# SigueLinea-final-SIN-PLANO-GND.net
KiCad netlist of a schematic drawn in EAGLE
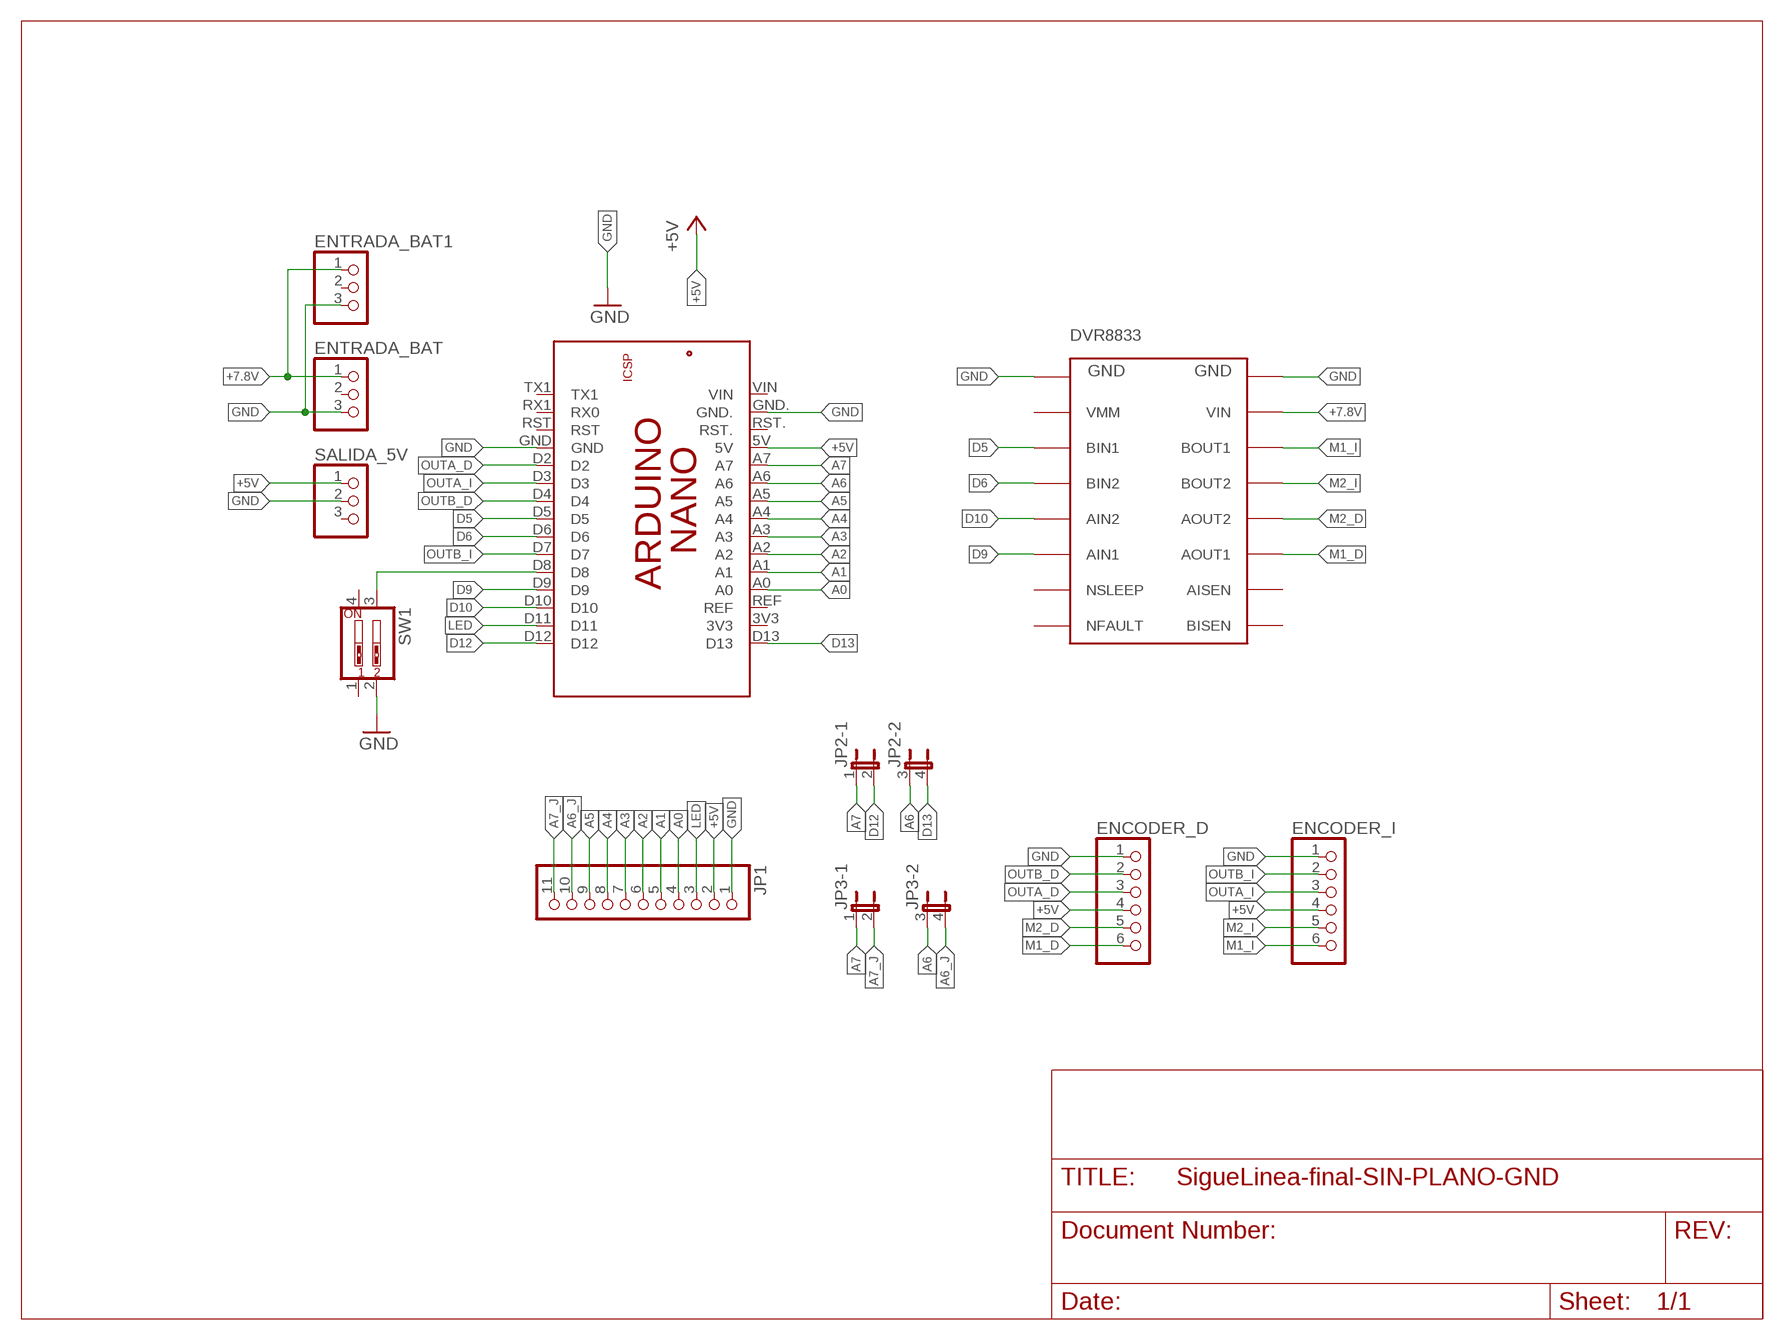
[diagram p0: schematic, sheet 1]

(export (version "E")
  (design (tool "Eeschema 10.0.6"))
  (components
    (comp (ref "DVR8833")
      (value "DRV8833")
      (footprint "eagle-import:DRV8833")
      (libsource (lib "eagle-import") (part "DRV8833"))
    )
    (comp (ref "ENCODER_D")
      (value "PINHD-1X6")
      (footprint "eagle-import:1X06")
      (libsource (lib "eagle-import") (part "PINHD-1X6"))
    )
    (comp (ref "ENCODER_I")
      (value "PINHD-1X6")
      (footprint "eagle-import:1X06")
      (libsource (lib "eagle-import") (part "PINHD-1X6"))
    )
    (comp (ref "ENTRADA_BAT")
      (value "PINHD-1X3")
      (footprint "eagle-import:1X03")
      (libsource (lib "eagle-import") (part "PINHD-1X3"))
    )
    (comp (ref "ENTRADA_BAT1")
      (value "PINHD-1X3")
      (footprint "eagle-import:1X03")
      (libsource (lib "eagle-import") (part "PINHD-1X3"))
    )
    (comp (ref "JP1")
      (value "PINHD-1X11")
      (footprint "eagle-import:1X11")
      (libsource (lib "eagle-import") (part "PINHD-1X11"))
    )
    (comp (ref "JP2")
      (value "JP2QE")
      (footprint "eagle-import:JP2Q")
      (libsource (lib "eagle-import") (part "JP2QE"))
    )
    (comp (ref "JP3")
      (value "JP2QE")
      (footprint "eagle-import:JP2Q")
      (libsource (lib "eagle-import") (part "JP2QE"))
    )
    (comp (ref "PCB1")
      (value "ARDUINO_NANO")
      (footprint "eagle-import:ARDUINO_NANO")
      (libsource (lib "eagle-import") (part "ARDUINO_NANO"))
    )
    (comp (ref "SALIDA_5V")
      (value "PINHD-1X3")
      (footprint "eagle-import:1X03")
      (libsource (lib "eagle-import") (part "PINHD-1X3"))
    )
    (comp (ref "SW1")
      (value "SW_DIP-2")
      (footprint "eagle-import:EDG-02")
      (libsource (lib "eagle-import") (part "SW_DIP-2"))
    )
  )
  (nets
    (net (code "1") (name "+5V") (class "Default")
      (node (ref "ENCODER_D") (pin "4") (pinfunction "4_4") (pintype "passive"))
      (node (ref "ENCODER_I") (pin "4") (pinfunction "4_4") (pintype "passive"))
      (node (ref "JP1") (pin "2") (pinfunction "2_2") (pintype "passive"))
      (node (ref "PCB1") (pin "5V") (pinfunction "5V_5V") (pintype "bidirectional"))
      (node (ref "SALIDA_5V") (pin "1") (pinfunction "1_1") (pintype "passive"))
    )
    (net (code "2") (name "+7.8V") (class "Default")
      (node (ref "DVR8833") (pin "VIN") (pinfunction "VIN_VIN") (pintype "bidirectional"))
      (node (ref "ENTRADA_BAT") (pin "1") (pinfunction "1_1") (pintype "passive"))
      (node (ref "ENTRADA_BAT1") (pin "1") (pinfunction "1_1") (pintype "passive"))
    )
    (net (code "3") (name "A0") (class "Default")
      (node (ref "JP1") (pin "4") (pinfunction "4_4") (pintype "passive"))
      (node (ref "PCB1") (pin "A0") (pinfunction "A0_A0") (pintype "bidirectional"))
    )
    (net (code "4") (name "A1") (class "Default")
      (node (ref "JP1") (pin "5") (pinfunction "5_5") (pintype "passive"))
      (node (ref "PCB1") (pin "A1") (pinfunction "A1_A1") (pintype "bidirectional"))
    )
    (net (code "5") (name "A2") (class "Default")
      (node (ref "JP1") (pin "6") (pinfunction "6_6") (pintype "passive"))
      (node (ref "PCB1") (pin "A2") (pinfunction "A2_A2") (pintype "bidirectional"))
    )
    (net (code "6") (name "A3") (class "Default")
      (node (ref "JP1") (pin "7") (pinfunction "7_7") (pintype "passive"))
      (node (ref "PCB1") (pin "A3") (pinfunction "A3_A3") (pintype "bidirectional"))
    )
    (net (code "7") (name "A4") (class "Default")
      (node (ref "JP1") (pin "8") (pinfunction "8_8") (pintype "passive"))
      (node (ref "PCB1") (pin "A4") (pinfunction "A4_A4") (pintype "bidirectional"))
    )
    (net (code "8") (name "A5") (class "Default")
      (node (ref "JP1") (pin "9") (pinfunction "9_9") (pintype "passive"))
      (node (ref "PCB1") (pin "A5") (pinfunction "A5_A5") (pintype "bidirectional"))
    )
    (net (code "9") (name "A6") (class "Default")
      (node (ref "JP2") (pin "3") (pinfunction "1_3") (pintype "passive"))
      (node (ref "JP3") (pin "3") (pinfunction "1_3") (pintype "passive"))
      (node (ref "PCB1") (pin "A6") (pinfunction "A6_A6") (pintype "bidirectional"))
    )
    (net (code "10") (name "A6_J") (class "Default")
      (node (ref "JP1") (pin "10") (pinfunction "10_10") (pintype "passive"))
      (node (ref "JP3") (pin "4") (pinfunction "2_4") (pintype "passive"))
    )
    (net (code "11") (name "A7") (class "Default")
      (node (ref "JP2") (pin "1") (pinfunction "1_1") (pintype "passive"))
      (node (ref "JP3") (pin "1") (pinfunction "1_1") (pintype "passive"))
      (node (ref "PCB1") (pin "A7") (pinfunction "A7_A7") (pintype "bidirectional"))
    )
    (net (code "12") (name "A7_J") (class "Default")
      (node (ref "JP1") (pin "11") (pinfunction "11_11") (pintype "passive"))
      (node (ref "JP3") (pin "2") (pinfunction "2_2") (pintype "passive"))
    )
    (net (code "13") (name "D5") (class "Default")
      (node (ref "DVR8833") (pin "BIN1") (pinfunction "BIN1_BIN1") (pintype "bidirectional"))
      (node (ref "PCB1") (pin "D5") (pinfunction "D5_D5") (pintype "bidirectional"))
    )
    (net (code "14") (name "D6") (class "Default")
      (node (ref "DVR8833") (pin "BIN2") (pinfunction "BIN2_BIN2") (pintype "bidirectional"))
      (node (ref "PCB1") (pin "D6") (pinfunction "D6_D6") (pintype "bidirectional"))
    )
    (net (code "15") (name "D9") (class "Default")
      (node (ref "DVR8833") (pin "AIN1") (pinfunction "AIN1_AIN1") (pintype "bidirectional"))
      (node (ref "PCB1") (pin "D9") (pinfunction "D9_D9") (pintype "bidirectional"))
    )
    (net (code "16") (name "D10") (class "Default")
      (node (ref "DVR8833") (pin "AIN2") (pinfunction "AIN2_AIN2") (pintype "bidirectional"))
      (node (ref "PCB1") (pin "D10") (pinfunction "D10_D10") (pintype "bidirectional"))
    )
    (net (code "17") (name "D12") (class "Default")
      (node (ref "JP2") (pin "2") (pinfunction "2_2") (pintype "passive"))
      (node (ref "PCB1") (pin "D12") (pinfunction "D12_D12") (pintype "bidirectional"))
    )
    (net (code "18") (name "D13") (class "Default")
      (node (ref "JP2") (pin "4") (pinfunction "2_4") (pintype "passive"))
      (node (ref "PCB1") (pin "D13") (pinfunction "D13_D13") (pintype "bidirectional"))
    )
    (net (code "19") (name "GND") (class "Default")
      (node (ref "DVR8833") (pin "GND1") (pinfunction "GND1_GND1") (pintype "bidirectional"))
      (node (ref "DVR8833") (pin "GND2") (pinfunction "GND2_GND2") (pintype "bidirectional"))
      (node (ref "ENCODER_D") (pin "1") (pinfunction "1_1") (pintype "passive"))
      (node (ref "ENCODER_I") (pin "1") (pinfunction "1_1") (pintype "passive"))
      (node (ref "ENTRADA_BAT") (pin "3") (pinfunction "3_3") (pintype "passive"))
      (node (ref "ENTRADA_BAT1") (pin "3") (pinfunction "3_3") (pintype "passive"))
      (node (ref "JP1") (pin "1") (pinfunction "1_1") (pintype "passive"))
      (node (ref "PCB1") (pin "GND") (pinfunction "GND_GND") (pintype "bidirectional"))
      (node (ref "PCB1") (pin "GND.") (pinfunction "GND._GND.") (pintype "bidirectional"))
      (node (ref "SALIDA_5V") (pin "2") (pinfunction "2_2") (pintype "passive"))
      (node (ref "SW1") (pin "2") (pinfunction "2_2") (pintype "passive"))
    )
    (net (code "20") (name "LED") (class "Default")
      (node (ref "JP1") (pin "3") (pinfunction "3_3") (pintype "passive"))
      (node (ref "PCB1") (pin "D11") (pinfunction "D11_D11") (pintype "bidirectional"))
    )
    (net (code "21") (name "M1_D") (class "Default")
      (node (ref "DVR8833") (pin "AOUT1") (pinfunction "AOUT1_AOUT1") (pintype "bidirectional"))
      (node (ref "ENCODER_D") (pin "6") (pinfunction "6_6") (pintype "passive"))
    )
    (net (code "22") (name "M1_I") (class "Default")
      (node (ref "DVR8833") (pin "BOUT1") (pinfunction "BOUT1_BOUT1") (pintype "bidirectional"))
      (node (ref "ENCODER_I") (pin "6") (pinfunction "6_6") (pintype "passive"))
    )
    (net (code "23") (name "M2_D") (class "Default")
      (node (ref "DVR8833") (pin "AOUT2") (pinfunction "AOUT2_AOUT2") (pintype "bidirectional"))
      (node (ref "ENCODER_D") (pin "5") (pinfunction "5_5") (pintype "passive"))
    )
    (net (code "24") (name "M2_I") (class "Default")
      (node (ref "DVR8833") (pin "BOUT2") (pinfunction "BOUT2_BOUT2") (pintype "bidirectional"))
      (node (ref "ENCODER_I") (pin "5") (pinfunction "5_5") (pintype "passive"))
    )
    (net (code "25") (name "Net-(PCB1-PadD8)") (class "Default")
      (node (ref "PCB1") (pin "D8") (pinfunction "D8_D8") (pintype "bidirectional"))
      (node (ref "SW1") (pin "3") (pinfunction "3_3") (pintype "passive"))
    )
    (net (code "26") (name "OUTA_D") (class "Default")
      (node (ref "ENCODER_D") (pin "3") (pinfunction "3_3") (pintype "passive"))
      (node (ref "PCB1") (pin "D2") (pinfunction "D2_D2") (pintype "bidirectional"))
    )
    (net (code "27") (name "OUTA_I") (class "Default")
      (node (ref "ENCODER_I") (pin "3") (pinfunction "3_3") (pintype "passive"))
      (node (ref "PCB1") (pin "D3") (pinfunction "D3_D3") (pintype "bidirectional"))
    )
    (net (code "28") (name "OUTB_D") (class "Default")
      (node (ref "ENCODER_D") (pin "2") (pinfunction "2_2") (pintype "passive"))
      (node (ref "PCB1") (pin "D4") (pinfunction "D4_D4") (pintype "bidirectional"))
    )
    (net (code "29") (name "OUTB_I") (class "Default")
      (node (ref "ENCODER_I") (pin "2") (pinfunction "2_2") (pintype "passive"))
      (node (ref "PCB1") (pin "D7") (pinfunction "D7_D7") (pintype "bidirectional"))
    )
    (net (code "30") (name "unconnected-(DVR8833-PadAISEN)") (class "Default")
      (node (ref "DVR8833") (pin "AISEN") (pinfunction "AISEN_AISEN") (pintype "bidirectional"))
    )
    (net (code "31") (name "unconnected-(DVR8833-PadBISEN)") (class "Default")
      (node (ref "DVR8833") (pin "BISEN") (pinfunction "BISEN_BISEN") (pintype "bidirectional"))
    )
    (net (code "32") (name "unconnected-(DVR8833-PadNFAULT)") (class "Default")
      (node (ref "DVR8833") (pin "NFAULT") (pinfunction "NFAULT_NFAULT") (pintype "bidirectional"))
    )
    (net (code "33") (name "unconnected-(DVR8833-PadNSLEEP)") (class "Default")
      (node (ref "DVR8833") (pin "NSLEEP") (pinfunction "NSLEEP_NSLEEP") (pintype "bidirectional"))
    )
    (net (code "34") (name "unconnected-(DVR8833-PadVMM)") (class "Default")
      (node (ref "DVR8833") (pin "VMM") (pinfunction "VMM_VMM") (pintype "bidirectional"))
    )
    (net (code "35") (name "unconnected-(ENTRADA_BAT-Pad2)") (class "Default")
      (node (ref "ENTRADA_BAT") (pin "2") (pinfunction "2_2") (pintype "passive"))
    )
    (net (code "36") (name "unconnected-(ENTRADA_BAT1-Pad2)") (class "Default")
      (node (ref "ENTRADA_BAT1") (pin "2") (pinfunction "2_2") (pintype "passive"))
    )
    (net (code "37") (name "unconnected-(PCB1-Pad3V3)") (class "Default")
      (node (ref "PCB1") (pin "3V3") (pinfunction "3V3_3V3") (pintype "bidirectional"))
    )
    (net (code "38") (name "unconnected-(PCB1-PadREF)") (class "Default")
      (node (ref "PCB1") (pin "REF") (pinfunction "REF_REF") (pintype "bidirectional"))
    )
    (net (code "39") (name "unconnected-(PCB1-PadRST)") (class "Default")
      (node (ref "PCB1") (pin "RST") (pinfunction "RST_RST") (pintype "bidirectional"))
    )
    (net (code "40") (name "unconnected-(PCB1-PadRST.)") (class "Default")
      (node (ref "PCB1") (pin "RST.") (pinfunction "RST._RST.") (pintype "bidirectional"))
    )
    (net (code "41") (name "unconnected-(PCB1-PadTX1)") (class "Default")
      (node (ref "PCB1") (pin "TX1") (pinfunction "TX1_TX1") (pintype "bidirectional"))
    )
    (net (code "42") (name "unconnected-(PCB1-PadVIN)") (class "Default")
      (node (ref "PCB1") (pin "VIN") (pinfunction "VIN_VIN") (pintype "bidirectional"))
    )
    (net (code "43") (name "unconnected-(PCB1-RX0-PadRX1)") (class "Default")
      (node (ref "PCB1") (pin "RX1") (pinfunction "RX0_RX1") (pintype "bidirectional"))
    )
    (net (code "44") (name "unconnected-(SALIDA_5V-Pad3)") (class "Default")
      (node (ref "SALIDA_5V") (pin "3") (pinfunction "3_3") (pintype "passive"))
    )
    (net (code "45") (name "unconnected-(SW1-Pad1)") (class "Default")
      (node (ref "SW1") (pin "1") (pinfunction "1_1") (pintype "passive"))
    )
    (net (code "46") (name "unconnected-(SW1-Pad4)") (class "Default")
      (node (ref "SW1") (pin "4") (pinfunction "4_4") (pintype "passive"))
    )
  )
)
